# MadHatterSchematic.net
KiCad netlist of a schematic drawn in EAGLE
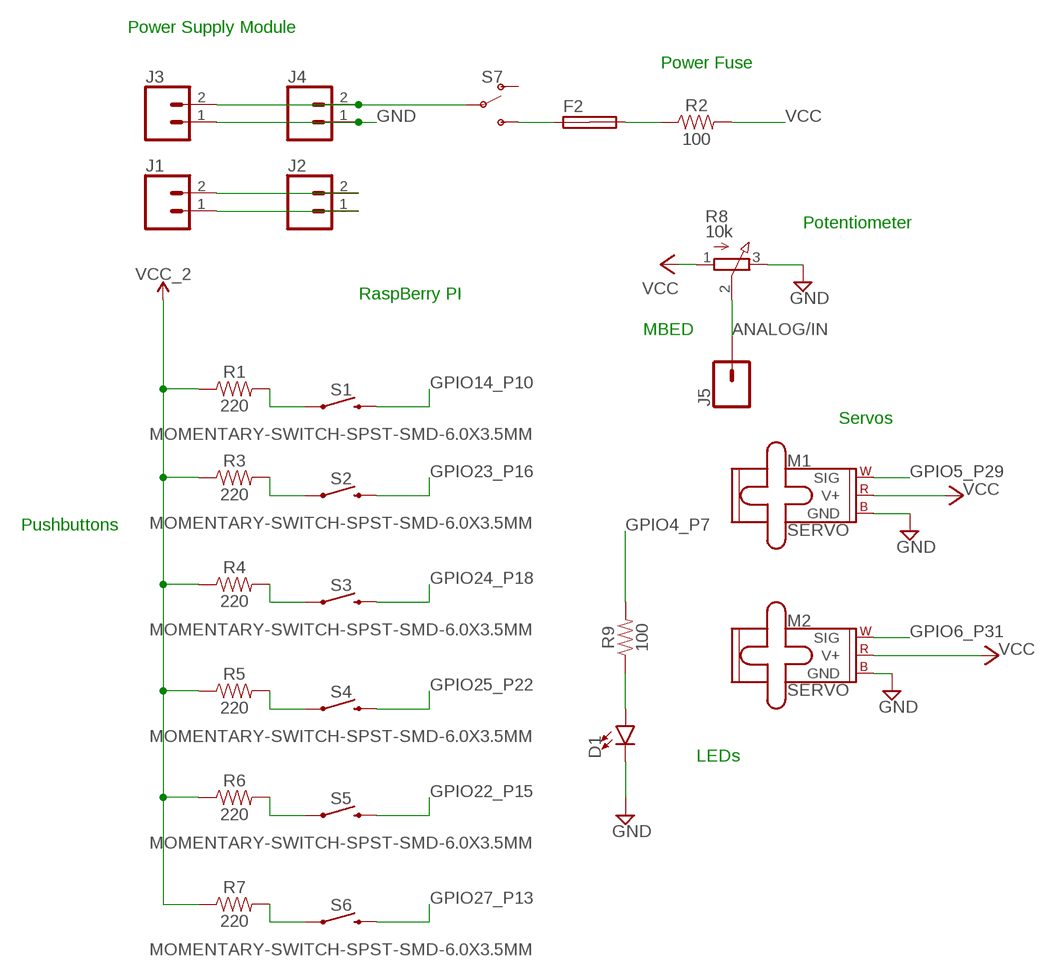
[diagram p0: schematic, sheet 1]

(export (version "E")
  (design (tool "Eeschema 10.0.6"))
  (components
    (comp (ref "D1")
      (value "LED0603")
      (footprint "eagle-import:LED-0603")
      (libsource (lib "eagle-import") (part "LED0603"))
    )
    (comp (ref "F2")
      (value "SHKOG")
      (footprint "eagle-import:SHKOG")
      (libsource (lib "eagle-import") (part "SHKOG"))
    )
    (comp (ref "J1")
      (value "CONN_02PTH_RA_FEMALE")
      (footprint "eagle-import:1X02_RA_PTH_FEMALE")
      (libsource (lib "eagle-import") (part "CONN_02PTH_RA_FEMALE"))
    )
    (comp (ref "J2")
      (value "CONN_02PTH_RA_FEMALE")
      (footprint "eagle-import:1X02_RA_PTH_FEMALE")
      (libsource (lib "eagle-import") (part "CONN_02PTH_RA_FEMALE"))
    )
    (comp (ref "J3")
      (value "CONN_02PTH_RA_FEMALE")
      (footprint "eagle-import:1X02_RA_PTH_FEMALE")
      (libsource (lib "eagle-import") (part "CONN_02PTH_RA_FEMALE"))
    )
    (comp (ref "J4")
      (value "CONN_02PTH_RA_FEMALE")
      (footprint "eagle-import:1X02_RA_PTH_FEMALE")
      (libsource (lib "eagle-import") (part "CONN_02PTH_RA_FEMALE"))
    )
    (comp (ref "J5")
      (value "CONN_01SNAP-FEMALE")
      (footprint "eagle-import:SNAP-FEMALE")
      (libsource (lib "eagle-import") (part "CONN_01SNAP-FEMALE"))
    )
    (comp (ref "M1")
      (value "SERVO")
      (footprint "eagle-import:1X03")
      (libsource (lib "eagle-import") (part "SERVO"))
    )
    (comp (ref "M2")
      (value "SERVO")
      (footprint "eagle-import:1X03")
      (libsource (lib "eagle-import") (part "SERVO"))
    )
    (comp (ref "R1")
      (value "220")
      (footprint "eagle-import:0402-TIGHT")
      (libsource (lib "eagle-import") (part "220OHM-0402-TIGHT-1/16W-1%"))
    )
    (comp (ref "R2")
      (value "100")
      (footprint "eagle-import:0402-TIGHT")
      (libsource (lib "eagle-import") (part "100OHM-0402-TIGHT-1/16W-1%"))
    )
    (comp (ref "R3")
      (value "220")
      (footprint "eagle-import:0402-TIGHT")
      (libsource (lib "eagle-import") (part "220OHM-0402-TIGHT-1/16W-1%"))
    )
    (comp (ref "R4")
      (value "220")
      (footprint "eagle-import:0402-TIGHT")
      (libsource (lib "eagle-import") (part "220OHM-0402-TIGHT-1/16W-1%"))
    )
    (comp (ref "R5")
      (value "220")
      (footprint "eagle-import:0402-TIGHT")
      (libsource (lib "eagle-import") (part "220OHM-0402-TIGHT-1/16W-1%"))
    )
    (comp (ref "R6")
      (value "220")
      (footprint "eagle-import:0402-TIGHT")
      (libsource (lib "eagle-import") (part "220OHM-0402-TIGHT-1/16W-1%"))
    )
    (comp (ref "R7")
      (value "220")
      (footprint "eagle-import:0402-TIGHT")
      (libsource (lib "eagle-import") (part "220OHM-0402-TIGHT-1/16W-1%"))
    )
    (comp (ref "R8")
      (value "10k")
      (footprint "eagle-import:3RP_1610N")
      (libsource (lib "eagle-import") (part "3RP/1610N"))
    )
    (comp (ref "R9")
      (value "100")
      (footprint "eagle-import:0402-TIGHT")
      (libsource (lib "eagle-import") (part "100OHM-0402-TIGHT-1/16W-1%"))
    )
    (comp (ref "S1")
      (value "MOMENTARY-SWITCH-SPST-SMD-6.0X3.5MM")
      (footprint "eagle-import:TACTILE_SWITCH_SMD_6.0X3.5MM")
      (libsource (lib "eagle-import") (part "MOMENTARY-SWITCH-SPST-SMD-6.0X3.5MM"))
    )
    (comp (ref "S2")
      (value "MOMENTARY-SWITCH-SPST-SMD-6.0X3.5MM")
      (footprint "eagle-import:TACTILE_SWITCH_SMD_6.0X3.5MM")
      (libsource (lib "eagle-import") (part "MOMENTARY-SWITCH-SPST-SMD-6.0X3.5MM"))
    )
    (comp (ref "S3")
      (value "MOMENTARY-SWITCH-SPST-SMD-6.0X3.5MM")
      (footprint "eagle-import:TACTILE_SWITCH_SMD_6.0X3.5MM")
      (libsource (lib "eagle-import") (part "MOMENTARY-SWITCH-SPST-SMD-6.0X3.5MM"))
    )
    (comp (ref "S4")
      (value "MOMENTARY-SWITCH-SPST-SMD-6.0X3.5MM")
      (footprint "eagle-import:TACTILE_SWITCH_SMD_6.0X3.5MM")
      (libsource (lib "eagle-import") (part "MOMENTARY-SWITCH-SPST-SMD-6.0X3.5MM"))
    )
    (comp (ref "S5")
      (value "MOMENTARY-SWITCH-SPST-SMD-6.0X3.5MM")
      (footprint "eagle-import:TACTILE_SWITCH_SMD_6.0X3.5MM")
      (libsource (lib "eagle-import") (part "MOMENTARY-SWITCH-SPST-SMD-6.0X3.5MM"))
    )
    (comp (ref "S6")
      (value "MOMENTARY-SWITCH-SPST-SMD-6.0X3.5MM")
      (footprint "eagle-import:TACTILE_SWITCH_SMD_6.0X3.5MM")
      (libsource (lib "eagle-import") (part "MOMENTARY-SWITCH-SPST-SMD-6.0X3.5MM"))
    )
    (comp (ref "S7")
      (value "SWITCH-SPDT-PTH-11.6X4.0MM")
      (footprint "eagle-import:SWITCH_SPDT_PTH_11.6X4.0MM")
      (libsource (lib "eagle-import") (part "SWITCH-SPDT-PTH-11.6X4.0MM"))
    )
  )
  (nets
    (net (code "1") (name "/ANALOG{slash}IN") (class "Default")
      (node (ref "J5") (pin "1") (pinfunction "1_1") (pintype "passive"))
      (node (ref "R8") (pin "2") (pinfunction "S_2") (pintype "passive"))
    )
    (net (code "2") (name "/GPIO4_P7") (class "Default")
      (node (ref "R9") (pin "2") (pinfunction "2_2") (pintype "passive"))
    )
    (net (code "3") (name "/GPIO5_P29") (class "Default")
      (node (ref "M1") (pin "1") (pinfunction "SIG_1") (pintype "bidirectional"))
    )
    (net (code "4") (name "/GPIO6_P31") (class "Default")
      (node (ref "M2") (pin "1") (pinfunction "SIG_1") (pintype "bidirectional"))
    )
    (net (code "5") (name "/GPIO14_P10") (class "Default")
      (node (ref "S1") (pin "2") (pinfunction "2_2") (pintype "passive"))
    )
    (net (code "6") (name "/GPIO22_P15") (class "Default")
      (node (ref "S5") (pin "2") (pinfunction "2_2") (pintype "passive"))
    )
    (net (code "7") (name "/GPIO23_P16") (class "Default")
      (node (ref "S2") (pin "2") (pinfunction "2_2") (pintype "passive"))
    )
    (net (code "8") (name "/GPIO24_P18") (class "Default")
      (node (ref "S3") (pin "2") (pinfunction "2_2") (pintype "passive"))
    )
    (net (code "9") (name "/GPIO25_P22") (class "Default")
      (node (ref "S4") (pin "2") (pinfunction "2_2") (pintype "passive"))
    )
    (net (code "10") (name "/GPIO27_P13") (class "Default")
      (node (ref "S6") (pin "2") (pinfunction "2_2") (pintype "passive"))
    )
    (net (code "11") (name "GND") (class "Default")
      (node (ref "D1") (pin "C") (pinfunction "C_C") (pintype "passive"))
      (node (ref "J1") (pin "1") (pinfunction "1_1") (pintype "passive"))
      (node (ref "J2") (pin "1") (pinfunction "1_1") (pintype "passive"))
      (node (ref "J3") (pin "1") (pinfunction "1_1") (pintype "passive"))
      (node (ref "J4") (pin "1") (pinfunction "1_1") (pintype "passive"))
      (node (ref "M1") (pin "3") (pinfunction "GND_3") (pintype "bidirectional"))
      (node (ref "M2") (pin "3") (pinfunction "GND_3") (pintype "bidirectional"))
      (node (ref "R8") (pin "3") (pinfunction "E_3") (pintype "passive"))
    )
    (net (code "12") (name "Net-(D1-PadA)") (class "Default")
      (node (ref "D1") (pin "A") (pinfunction "A_A") (pintype "passive"))
      (node (ref "R9") (pin "1") (pinfunction "1_1") (pintype "passive"))
    )
    (net (code "13") (name "Net-(F2-Pad2A)") (class "Default")
      (node (ref "F2") (pin "2A") (pinfunction "2A_2A") (pintype "passive"))
      (node (ref "R2") (pin "1") (pinfunction "1_1") (pintype "passive"))
    )
    (net (code "14") (name "Net-(R1-Pad2)") (class "Default")
      (node (ref "R1") (pin "2") (pinfunction "2_2") (pintype "passive"))
      (node (ref "S1") (pin "1") (pinfunction "1_1") (pintype "passive"))
    )
    (net (code "15") (name "Net-(R3-Pad2)") (class "Default")
      (node (ref "R3") (pin "2") (pinfunction "2_2") (pintype "passive"))
      (node (ref "S2") (pin "1") (pinfunction "1_1") (pintype "passive"))
    )
    (net (code "16") (name "Net-(R4-Pad2)") (class "Default")
      (node (ref "R4") (pin "2") (pinfunction "2_2") (pintype "passive"))
      (node (ref "S3") (pin "1") (pinfunction "1_1") (pintype "passive"))
    )
    (net (code "17") (name "Net-(R5-Pad2)") (class "Default")
      (node (ref "R5") (pin "2") (pinfunction "2_2") (pintype "passive"))
      (node (ref "S4") (pin "1") (pinfunction "1_1") (pintype "passive"))
    )
    (net (code "18") (name "Net-(R6-Pad2)") (class "Default")
      (node (ref "R6") (pin "2") (pinfunction "2_2") (pintype "passive"))
      (node (ref "S5") (pin "1") (pinfunction "1_1") (pintype "passive"))
    )
    (net (code "19") (name "Net-(R7-Pad2)") (class "Default")
      (node (ref "R7") (pin "2") (pinfunction "2_2") (pintype "passive"))
      (node (ref "S6") (pin "1") (pinfunction "1_1") (pintype "passive"))
    )
    (net (code "20") (name "Net-(S7-S)") (class "Default")
      (node (ref "F2") (pin "1A") (pinfunction "1A_1A") (pintype "passive"))
      (node (ref "S7") (pin "3") (pinfunction "S_3") (pintype "passive"))
    )
    (net (code "21") (name "VCC") (class "Default")
      (node (ref "J1") (pin "2") (pinfunction "2_2") (pintype "passive"))
      (node (ref "J2") (pin "2") (pinfunction "2_2") (pintype "passive"))
      (node (ref "J3") (pin "2") (pinfunction "2_2") (pintype "passive"))
      (node (ref "J4") (pin "2") (pinfunction "2_2") (pintype "passive"))
      (node (ref "M1") (pin "2") (pinfunction "V+_2") (pintype "bidirectional"))
      (node (ref "M2") (pin "2") (pinfunction "V+_2") (pintype "bidirectional"))
      (node (ref "R2") (pin "2") (pinfunction "2_2") (pintype "passive"))
      (node (ref "R8") (pin "1") (pinfunction "A_1") (pintype "passive"))
      (node (ref "S7") (pin "2") (pinfunction "P_2") (pintype "passive"))
    )
    (net (code "22") (name "VCC_2") (class "Default")
      (node (ref "R1") (pin "1") (pinfunction "1_1") (pintype "passive"))
      (node (ref "R3") (pin "1") (pinfunction "1_1") (pintype "passive"))
      (node (ref "R4") (pin "1") (pinfunction "1_1") (pintype "passive"))
      (node (ref "R5") (pin "1") (pinfunction "1_1") (pintype "passive"))
      (node (ref "R6") (pin "1") (pinfunction "1_1") (pintype "passive"))
      (node (ref "R7") (pin "1") (pinfunction "1_1") (pintype "passive"))
    )
    (net (code "23") (name "unconnected-(F2-Pad1B)") (class "Default")
      (node (ref "F2") (pin "1B") (pinfunction "1B_1B") (pintype "passive"))
    )
    (net (code "24") (name "unconnected-(F2-Pad2B)") (class "Default")
      (node (ref "F2") (pin "2B") (pinfunction "2B_2B") (pintype "passive"))
    )
    (net (code "25") (name "unconnected-(S7-O-Pad1)") (class "Default")
      (node (ref "S7") (pin "1") (pinfunction "O_1") (pintype "passive"))
    )
  )
)
